# Top.net
KiCad netlist of a schematic drawn in Altium Designer
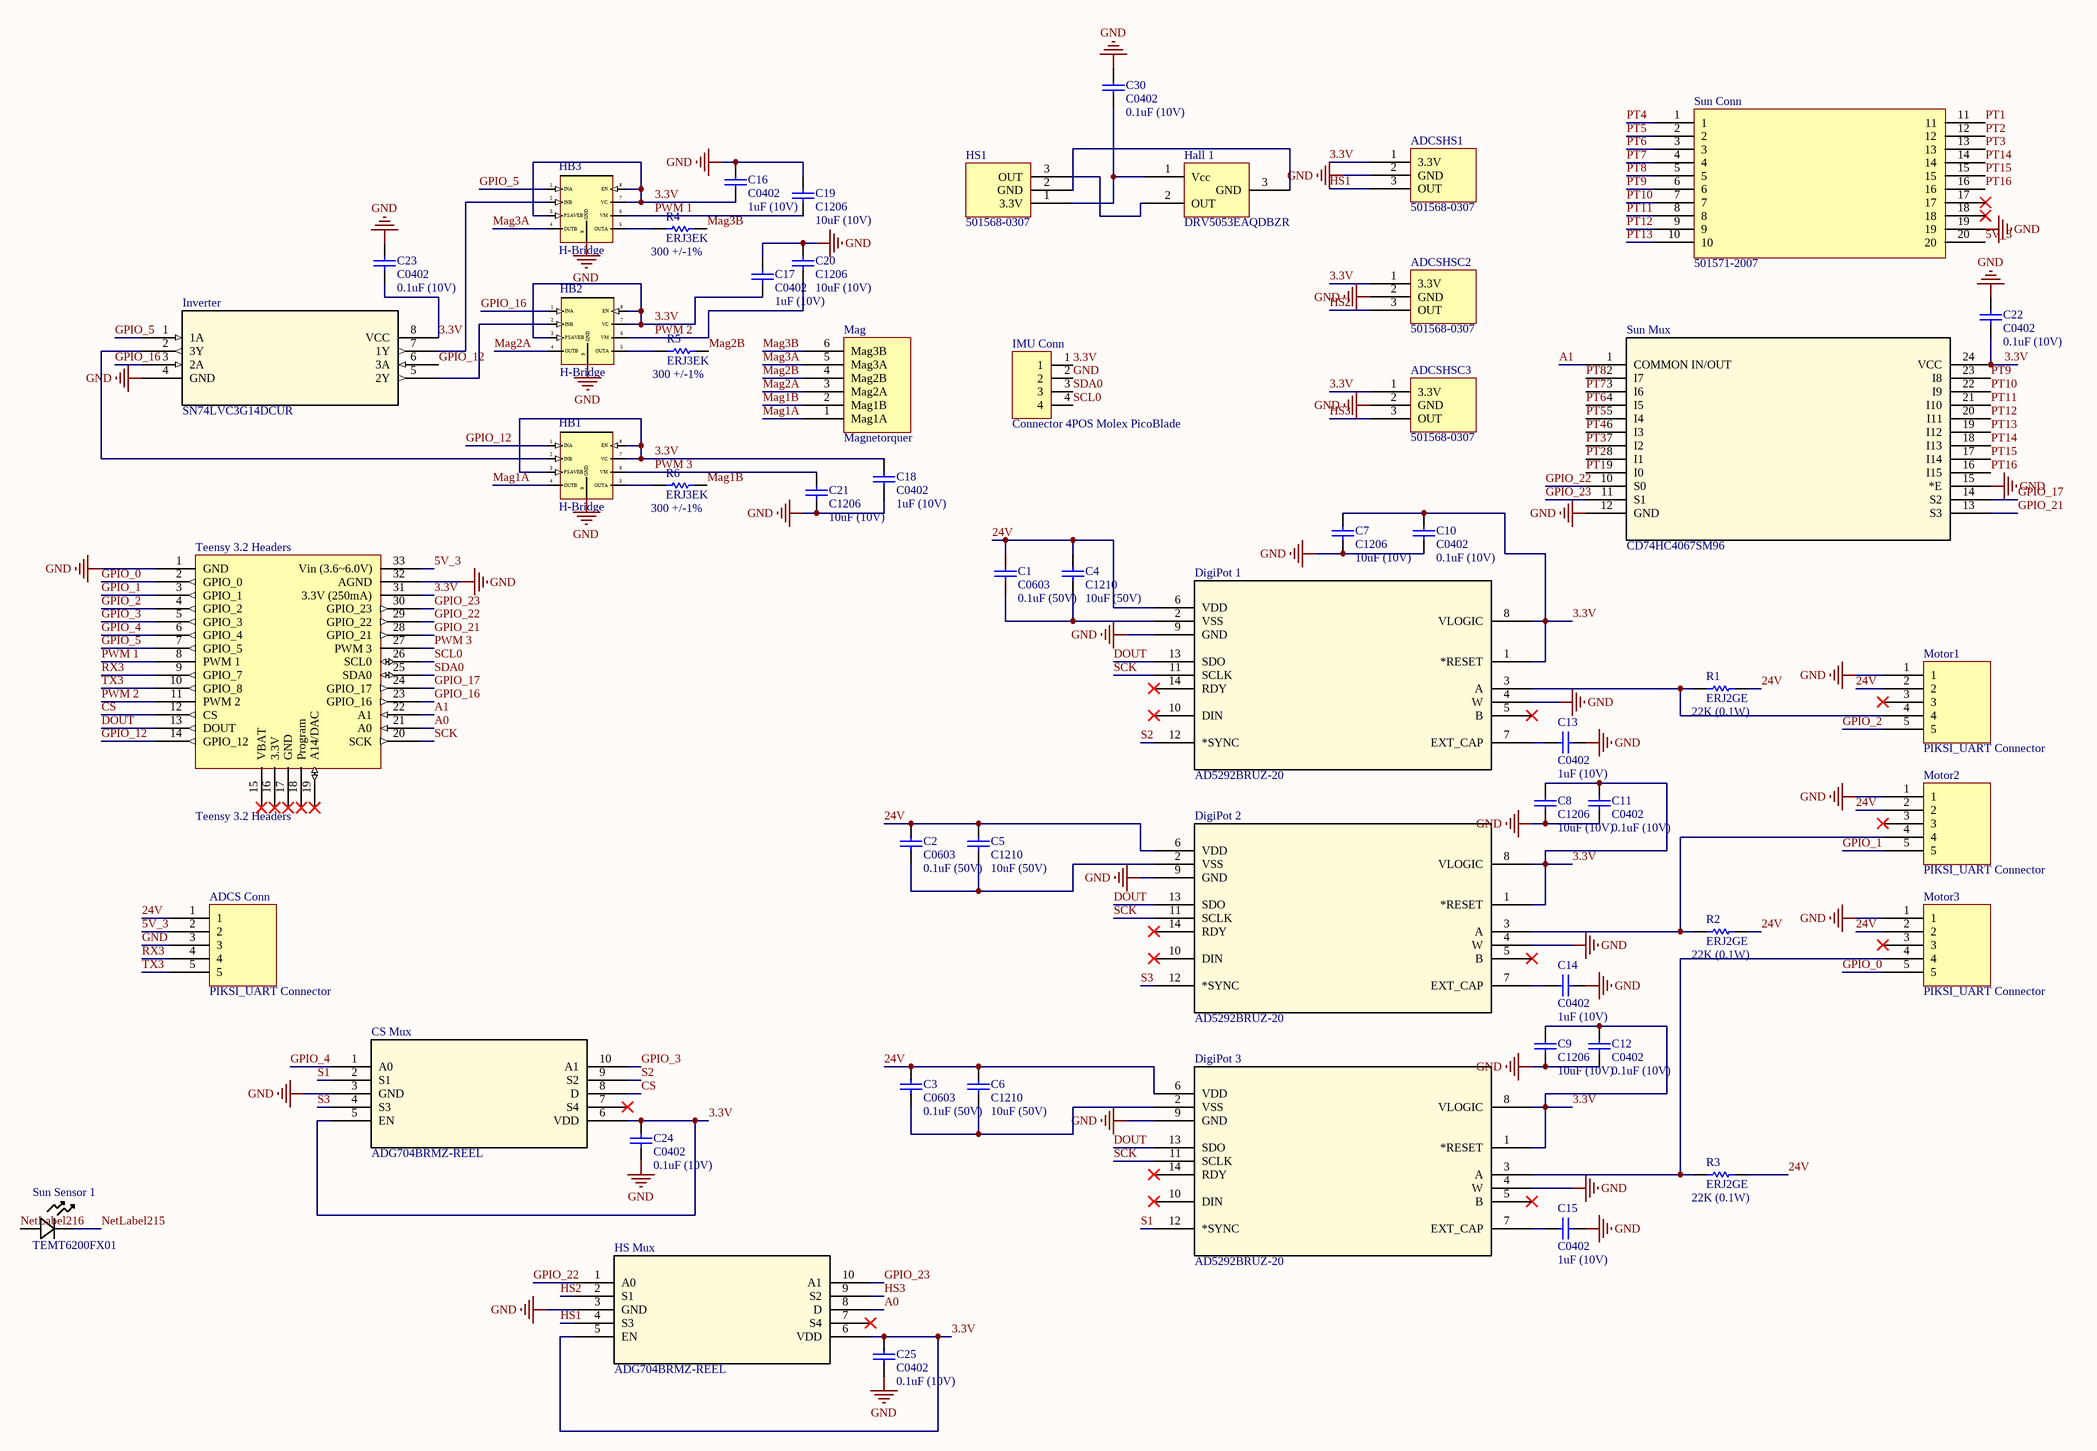
[diagram p0: Top.SchDoc]

(export (version "E")
  (design (tool "Eeschema 10.0.6"))
  (components
    (comp (ref "ADCS Conn")
      (value "PIKSI_UART Connector")
      (footprint "UmbilicalConnectors:Molex Picoblade 5 Pin")
      (description "Molex Picoblade 53261-0571")
      (libsource (lib "UmbilicalBoardV2") (part "PIKSI_UART Connector"))
    )
    (comp (ref "ADCSHS1")
      (value "501568-0307")
      (footprint "5015680307")
      (description "CONN HEADER 1MM 3POS")
      (libsource (lib "SchematicComponents") (part "501568-0307"))
    )
    (comp (ref "ADCSHSC2")
      (value "501568-0307")
      (footprint "5015680307")
      (description "CONN HEADER 1MM 3POS")
      (libsource (lib "SchematicComponents") (part "501568-0307"))
    )
    (comp (ref "ADCSHSC3")
      (value "501568-0307")
      (footprint "5015680307")
      (description "CONN HEADER 1MM 3POS")
      (libsource (lib "SchematicComponents") (part "501568-0307"))
    )
    (comp (ref "C1")
      (value "C0603")
      (footprint "0603")
      (description "Ceramic Chip Capacitor - Standard")
      (fields (field (name "ALTIUM_VALUE") "0.1uF (50V)") (field (name "PUBLISHER") "Altium Limited"))
      (libsource (lib "KEMET Chip Capacitor") (part "C0603"))
    )
    (comp (ref "C2")
      (value "C0603")
      (footprint "0603")
      (description "Ceramic Chip Capacitor - Standard")
      (fields (field (name "ALTIUM_VALUE") "0.1uF (50V)") (field (name "PUBLISHER") "Altium Limited"))
      (libsource (lib "KEMET Chip Capacitor") (part "C0603"))
    )
    (comp (ref "C3")
      (value "C0603")
      (footprint "0603")
      (description "Ceramic Chip Capacitor - Standard")
      (fields (field (name "ALTIUM_VALUE") "0.1uF (50V)") (field (name "PUBLISHER") "Altium Limited"))
      (libsource (lib "KEMET Chip Capacitor") (part "C0603"))
    )
    (comp (ref "C4")
      (value "C1210")
      (footprint "1210")
      (description "Ceramic Chip Capacitor - Standard")
      (fields (field (name "ALTIUM_VALUE") "10uF (50V)") (field (name "PUBLISHER") "Altium Limited"))
      (libsource (lib "KEMET Chip Capacitor") (part "C1210"))
    )
    (comp (ref "C5")
      (value "C1210")
      (footprint "1210")
      (description "Ceramic Chip Capacitor - Standard")
      (fields (field (name "ALTIUM_VALUE") "10uF (50V)") (field (name "PUBLISHER") "Altium Limited"))
      (libsource (lib "KEMET Chip Capacitor") (part "C1210"))
    )
    (comp (ref "C6")
      (value "C1210")
      (footprint "1210")
      (description "Ceramic Chip Capacitor - Standard")
      (fields (field (name "ALTIUM_VALUE") "10uF (50V)") (field (name "PUBLISHER") "Altium Limited"))
      (libsource (lib "KEMET Chip Capacitor") (part "C1210"))
    )
    (comp (ref "C7")
      (value "C1206")
      (footprint "1206")
      (description "Ceramic Chip Capacitor - Standard")
      (fields (field (name "ALTIUM_VALUE") "10uF (10V)") (field (name "PUBLISHER") "Altium Limited"))
      (libsource (lib "KEMET Chip Capacitor") (part "C1206"))
    )
    (comp (ref "C8")
      (value "C1206")
      (footprint "1206")
      (description "Ceramic Chip Capacitor - Standard")
      (fields (field (name "ALTIUM_VALUE") "10uF (10V)") (field (name "PUBLISHER") "Altium Limited"))
      (libsource (lib "KEMET Chip Capacitor") (part "C1206"))
    )
    (comp (ref "C9")
      (value "C1206")
      (footprint "1206")
      (description "Ceramic Chip Capacitor - Standard")
      (fields (field (name "ALTIUM_VALUE") "10uF (10V)") (field (name "PUBLISHER") "Altium Limited"))
      (libsource (lib "KEMET Chip Capacitor") (part "C1206"))
    )
    (comp (ref "C10")
      (value "C0402")
      (footprint "0402")
      (description "Ceramic Chip Capacitor - Standard")
      (fields (field (name "ALTIUM_VALUE") "0.1uF (10V)") (field (name "PUBLISHER") "Altium Limited"))
      (libsource (lib "KEMET Chip Capacitor") (part "C0402"))
    )
    (comp (ref "C11")
      (value "C0402")
      (footprint "0402")
      (description "Ceramic Chip Capacitor - Standard")
      (fields (field (name "ALTIUM_VALUE") "0.1uF (10V)") (field (name "PUBLISHER") "Altium Limited"))
      (libsource (lib "KEMET Chip Capacitor") (part "C0402"))
    )
    (comp (ref "C12")
      (value "C0402")
      (footprint "0402")
      (description "Ceramic Chip Capacitor - Standard")
      (fields (field (name "ALTIUM_VALUE") "0.1uF (10V)") (field (name "PUBLISHER") "Altium Limited"))
      (libsource (lib "KEMET Chip Capacitor") (part "C0402"))
    )
    (comp (ref "C13")
      (value "C0402")
      (footprint "0402")
      (description "Ceramic Chip Capacitor - Standard")
      (fields (field (name "ALTIUM_VALUE") "1uF (10V)") (field (name "PUBLISHER") "Altium Limited"))
      (libsource (lib "KEMET Chip Capacitor") (part "C0402"))
    )
    (comp (ref "C14")
      (value "C0402")
      (footprint "0402")
      (description "Ceramic Chip Capacitor - Standard")
      (fields (field (name "ALTIUM_VALUE") "1uF (10V)") (field (name "PUBLISHER") "Altium Limited"))
      (libsource (lib "KEMET Chip Capacitor") (part "C0402"))
    )
    (comp (ref "C15")
      (value "C0402")
      (footprint "0402")
      (description "Ceramic Chip Capacitor - Standard")
      (fields (field (name "ALTIUM_VALUE") "1uF (10V)") (field (name "PUBLISHER") "Altium Limited"))
      (libsource (lib "KEMET Chip Capacitor") (part "C0402"))
    )
    (comp (ref "C16")
      (value "C0402")
      (footprint "0402")
      (description "Ceramic Chip Capacitor - Standard")
      (fields (field (name "ALTIUM_VALUE") "1uF (10V)") (field (name "PUBLISHER") "Altium Limited"))
      (libsource (lib "KEMET Chip Capacitor") (part "C0402"))
    )
    (comp (ref "C17")
      (value "C0402")
      (footprint "0402")
      (description "Ceramic Chip Capacitor - Standard")
      (fields (field (name "ALTIUM_VALUE") "1uF (10V)") (field (name "PUBLISHER") "Altium Limited"))
      (libsource (lib "KEMET Chip Capacitor") (part "C0402"))
    )
    (comp (ref "C18")
      (value "C0402")
      (footprint "0402")
      (description "Ceramic Chip Capacitor - Standard")
      (fields (field (name "ALTIUM_VALUE") "1uF (10V)") (field (name "PUBLISHER") "Altium Limited"))
      (libsource (lib "KEMET Chip Capacitor") (part "C0402"))
    )
    (comp (ref "C19")
      (value "C1206")
      (footprint "1206")
      (description "Ceramic Chip Capacitor - Standard")
      (fields (field (name "ALTIUM_VALUE") "10uF (10V)") (field (name "PUBLISHER") "Altium Limited"))
      (libsource (lib "KEMET Chip Capacitor") (part "C1206"))
    )
    (comp (ref "C20")
      (value "C1206")
      (footprint "1206")
      (description "Ceramic Chip Capacitor - Standard")
      (fields (field (name "ALTIUM_VALUE") "10uF (10V)") (field (name "PUBLISHER") "Altium Limited"))
      (libsource (lib "KEMET Chip Capacitor") (part "C1206"))
    )
    (comp (ref "C21")
      (value "C1206")
      (footprint "1206")
      (description "Ceramic Chip Capacitor - Standard")
      (fields (field (name "ALTIUM_VALUE") "10uF (10V)") (field (name "PUBLISHER") "Altium Limited"))
      (libsource (lib "KEMET Chip Capacitor") (part "C1206"))
    )
    (comp (ref "C22")
      (value "C0402")
      (footprint "0402")
      (description "Ceramic Chip Capacitor - Standard")
      (fields (field (name "ALTIUM_VALUE") "0.1uF (10V)") (field (name "PUBLISHER") "Altium Limited"))
      (libsource (lib "KEMET Chip Capacitor") (part "C0402"))
    )
    (comp (ref "C23")
      (value "C0402")
      (footprint "0402")
      (description "Ceramic Chip Capacitor - Standard")
      (fields (field (name "ALTIUM_VALUE") "0.1uF (10V)") (field (name "PUBLISHER") "Altium Limited"))
      (libsource (lib "KEMET Chip Capacitor") (part "C0402"))
    )
    (comp (ref "C24")
      (value "C0402")
      (footprint "0402")
      (description "Ceramic Chip Capacitor - Standard")
      (fields (field (name "ALTIUM_VALUE") "0.1uF (10V)") (field (name "PUBLISHER") "Altium Limited"))
      (libsource (lib "KEMET Chip Capacitor") (part "C0402"))
    )
    (comp (ref "C25")
      (value "C0402")
      (footprint "0402")
      (description "Ceramic Chip Capacitor - Standard")
      (fields (field (name "ALTIUM_VALUE") "0.1uF (10V)") (field (name "PUBLISHER") "Altium Limited"))
      (libsource (lib "KEMET Chip Capacitor") (part "C0402"))
    )
    (comp (ref "C30")
      (value "C0402")
      (footprint "0402")
      (description "Ceramic Chip Capacitor - Standard")
      (fields (field (name "ALTIUM_VALUE") "0.1uF (10V)") (field (name "PUBLISHER") "Altium Limited"))
      (libsource (lib "KEMET Chip Capacitor") (part "C0402"))
    )
    (comp (ref "CS Mux")
      (value "ADG704BRMZ-REEL")
      (footprint "ADG704BRMZ-REEL")
      (libsource (lib "SchematicComponents") (part "ADG704BRMZ-REEL"))
    )
    (comp (ref "DigiPot 1")
      (value "AD5292BRUZ-20")
      (footprint "AD5292BRUZ-20")
      (description "20K DigiPot 1024POS")
      (libsource (lib "SchematicComponents") (part "AD5292BRUZ-20"))
    )
    (comp (ref "DigiPot 2")
      (value "AD5292BRUZ-20")
      (footprint "AD5292BRUZ-20")
      (description "20K DigiPot 1024POS")
      (libsource (lib "SchematicComponents") (part "AD5292BRUZ-20"))
    )
    (comp (ref "DigiPot 3")
      (value "AD5292BRUZ-20")
      (footprint "AD5292BRUZ-20")
      (description "20K DigiPot 1024POS")
      (libsource (lib "SchematicComponents") (part "AD5292BRUZ-20"))
    )
    (comp (ref "Hall 1")
      (value "DRV5053EAQDBZR")
      (footprint "DRV5053EAQDBZR")
      (description "Hall Sensor Linear SOT-23-3")
      (libsource (lib "SchematicComponents") (part "DRV5053EAQDBZR"))
    )
    (comp (ref "HB1")
      (value "H-Bridge")
      (footprint "AP1017")
      (libsource (lib "SchematicComponents") (part "AP1017AEN"))
    )
    (comp (ref "HB2")
      (value "H-Bridge")
      (footprint "AP1017")
      (libsource (lib "SchematicComponents") (part "AP1017AEN"))
    )
    (comp (ref "HB3")
      (value "H-Bridge")
      (footprint "AP1017")
      (libsource (lib "SchematicComponents") (part "AP1017AEN"))
    )
    (comp (ref "HS Mux")
      (value "ADG704BRMZ-REEL")
      (footprint "ADG704BRMZ-REEL")
      (libsource (lib "SchematicComponents") (part "ADG704BRMZ-REEL"))
    )
    (comp (ref "HS1")
      (value "501568-0307")
      (footprint "5015680307")
      (description "CONN HEADER 1MM 3POS")
      (libsource (lib "") (part "501568-0307_1"))
    )
    (comp (ref "IMU Conn")
      (value "Connector 4POS Molex PicoBlade")
      (footprint "532610471")
      (libsource (lib "SchematicComponents") (part "532610471"))
    )
    (comp (ref "Inverter")
      (value "SN74LVC3G14DCUR")
      (footprint "SN74LVC3G14DCUR")
      (libsource (lib "SchematicComponents") (part "SN74LVC3G14DCUR"))
    )
    (comp (ref "Mag")
      (value "Magnetorquer")
      (description "Molex 70553-0005")
      (libsource (lib "UmbilicalBoardV2") (part "PressureConnector"))
    )
    (comp (ref "Motor1")
      (value "PIKSI_UART Connector")
      (footprint "UmbilicalConnectors:Molex Picoblade 5 Pin")
      (description "Molex Picoblade 53261-0571")
      (libsource (lib "UmbilicalBoardV2") (part "PIKSI_UART Connector"))
    )
    (comp (ref "Motor2")
      (value "PIKSI_UART Connector")
      (footprint "UmbilicalConnectors:Molex Picoblade 5 Pin")
      (description "Molex Picoblade 53261-0571")
      (libsource (lib "UmbilicalBoardV2") (part "PIKSI_UART Connector"))
    )
    (comp (ref "Motor3")
      (value "PIKSI_UART Connector")
      (footprint "UmbilicalConnectors:Molex Picoblade 5 Pin")
      (description "Molex Picoblade 53261-0571")
      (libsource (lib "UmbilicalBoardV2") (part "PIKSI_UART Connector"))
    )
    (comp (ref "R1")
      (value "ERJ2GE")
      (footprint "2-0402")
      (description "Thick Film Chip Resistor, 1 Ohm to 2.2M Ohm Range, 5% Tolerance, 0402 Size, 0.063 W")
      (fields (field (name "ALTIUM_VALUE") "22K (0.1W)") (field (name "PUBLISHER") "Altium Limited"))
      (libsource (lib "Panasonic Resistor") (part "ERJ2GE"))
    )
    (comp (ref "R2")
      (value "ERJ2GE")
      (footprint "2-0402")
      (description "Thick Film Chip Resistor, 1 Ohm to 2.2M Ohm Range, 5% Tolerance, 0402 Size, 0.063 W")
      (fields (field (name "ALTIUM_VALUE") "22K (0.1W)") (field (name "PUBLISHER") "Altium Limited"))
      (libsource (lib "Panasonic Resistor") (part "ERJ2GE"))
    )
    (comp (ref "R3")
      (value "ERJ2GE")
      (footprint "2-0402")
      (description "Thick Film Chip Resistor, 1 Ohm to 2.2M Ohm Range, 5% Tolerance, 0402 Size, 0.063 W")
      (fields (field (name "ALTIUM_VALUE") "22K (0.1W)") (field (name "PUBLISHER") "Altium Limited"))
      (libsource (lib "Panasonic Resistor") (part "ERJ2GE"))
    )
    (comp (ref "R4")
      (value "ERJ3EK")
      (footprint "3-0603")
      (fields (field (name "RESISTANCE") "300 +/-1%") (field (name "PUBLISHER") "Altium Limited"))
      (libsource (lib "Panasonic Resistor") (part "ERJ3EK"))
    )
    (comp (ref "R5")
      (value "ERJ3EK")
      (footprint "3-0603")
      (fields (field (name "RESISTANCE") "300 +/-1%") (field (name "PUBLISHER") "Altium Limited"))
      (libsource (lib "Panasonic Resistor") (part "ERJ3EK"))
    )
    (comp (ref "R6")
      (value "ERJ3EK")
      (footprint "3-0603")
      (fields (field (name "RESISTANCE") "300 +/-1%") (field (name "PUBLISHER") "Altium Limited"))
      (libsource (lib "Panasonic Resistor") (part "ERJ3EK"))
    )
    (comp (ref "Sun Conn")
      (value "501571-2007")
      (footprint "501571-2007 20Pos Conn")
      (description "Pico-Clasp 1.0mm 20POS")
      (libsource (lib "SchematicComponents") (part "501571-2007"))
    )
    (comp (ref "Sun Mux")
      (value "CD74HC4067SM96")
      (footprint "CD74HC4067SM96")
      (libsource (lib "SchematicComponents") (part "CD74HC4067SM96"))
    )
    (comp (ref "Sun Sensor 1")
      (value "TEMT6200FX01")
      (footprint "Phototransistor")
      (libsource (lib "SchematicComponents") (part "TEMT6200FX01"))
    )
    (comp (ref "Teensy 3.2 Headers")
      (value "Teensy 3.2 Headers")
      (footprint "Teensy 3.2 with Headers")
      (libsource (lib "SchematicComponents") (part "Teensy 3.2 Headers"))
    )
  )
  (nets
    (net (code "1") (name "/3.3V") (class "Default")
      (node (ref "ADCSHS1") (pin "1") (pinfunction "3.3V_1") (pintype "power_in"))
      (node (ref "ADCSHSC2") (pin "1") (pinfunction "3.3V_1") (pintype "power_in"))
      (node (ref "ADCSHSC3") (pin "1") (pinfunction "3.3V_1") (pintype "power_in"))
      (node (ref "C10") (pin "2") (pinfunction "2_2") (pintype "passive"))
      (node (ref "C11") (pin "2") (pinfunction "2_2") (pintype "passive"))
      (node (ref "C12") (pin "2") (pinfunction "2_2") (pintype "passive"))
      (node (ref "C16") (pin "1") (pinfunction "1_1") (pintype "passive"))
      (node (ref "C17") (pin "1") (pinfunction "1_1") (pintype "passive"))
      (node (ref "C18") (pin "2") (pinfunction "2_2") (pintype "passive"))
      (node (ref "C22") (pin "1") (pinfunction "1_1") (pintype "passive"))
      (node (ref "C23") (pin "1") (pinfunction "1_1") (pintype "passive"))
      (node (ref "C24") (pin "2") (pinfunction "2_2") (pintype "passive"))
      (node (ref "C25") (pin "2") (pinfunction "2_2") (pintype "passive"))
      (node (ref "C7") (pin "2") (pinfunction "2_2") (pintype "passive"))
      (node (ref "C8") (pin "2") (pinfunction "2_2") (pintype "passive"))
      (node (ref "C9") (pin "2") (pinfunction "2_2") (pintype "passive"))
      (node (ref "CS Mux") (pin "5") (pinfunction "EN_5") (pintype "passive"))
      (node (ref "CS Mux") (pin "6") (pinfunction "VDD_6") (pintype "power_in"))
      (node (ref "DigiPot 1") (pin "1") (pinfunction "*RESET_1") (pintype "passive"))
      (node (ref "DigiPot 1") (pin "8") (pinfunction "VLOGIC_8") (pintype "passive"))
      (node (ref "DigiPot 2") (pin "1") (pinfunction "*RESET_1") (pintype "passive"))
      (node (ref "DigiPot 2") (pin "8") (pinfunction "VLOGIC_8") (pintype "passive"))
      (node (ref "DigiPot 3") (pin "1") (pinfunction "*RESET_1") (pintype "passive"))
      (node (ref "DigiPot 3") (pin "8") (pinfunction "VLOGIC_8") (pintype "passive"))
      (node (ref "HB1") (pin "3") (pinfunction "PSAVEB_3") (pintype "input"))
      (node (ref "HB1") (pin "7") (pinfunction "VC_7") (pintype "power_in"))
      (node (ref "HB1") (pin "8") (pinfunction "EN_8") (pintype "input"))
      (node (ref "HB2") (pin "3") (pinfunction "PSAVEB_3") (pintype "input"))
      (node (ref "HB2") (pin "7") (pinfunction "VC_7") (pintype "power_in"))
      (node (ref "HB2") (pin "8") (pinfunction "EN_8") (pintype "input"))
      (node (ref "HB3") (pin "3") (pinfunction "PSAVEB_3") (pintype "input"))
      (node (ref "HB3") (pin "7") (pinfunction "VC_7") (pintype "power_in"))
      (node (ref "HB3") (pin "8") (pinfunction "EN_8") (pintype "input"))
      (node (ref "HS Mux") (pin "5") (pinfunction "EN_5") (pintype "passive"))
      (node (ref "HS Mux") (pin "6") (pinfunction "VDD_6") (pintype "power_in"))
      (node (ref "IMU Conn") (pin "1") (pinfunction "1_1") (pintype "passive"))
      (node (ref "Inverter") (pin "8") (pinfunction "VCC_8") (pintype "power_in"))
      (node (ref "Sun Mux") (pin "24") (pinfunction "VCC_24") (pintype "power_in"))
      (node (ref "Teensy 3.2 Headers") (pin "31") (pinfunction "3.3V_(250mA)_31") (pintype "power_in"))
    )
    (net (code "2") (name "/5V_3") (class "Default")
      (node (ref "ADCS Conn") (pin "2") (pinfunction "2_2") (pintype "passive"))
      (node (ref "Sun Conn") (pin "20") (pinfunction "20_20") (pintype "passive"))
      (node (ref "Teensy 3.2 Headers") (pin "33") (pinfunction "Vin_(3.6~6.0V)_33") (pintype "power_in"))
    )
    (net (code "3") (name "/24V") (class "Default")
      (node (ref "ADCS Conn") (pin "1") (pinfunction "1_1") (pintype "passive"))
      (node (ref "C1") (pin "2") (pinfunction "2_2") (pintype "passive"))
      (node (ref "C2") (pin "2") (pinfunction "2_2") (pintype "passive"))
      (node (ref "C3") (pin "2") (pinfunction "2_2") (pintype "passive"))
      (node (ref "C4") (pin "2") (pinfunction "2_2") (pintype "passive"))
      (node (ref "C5") (pin "2") (pinfunction "2_2") (pintype "passive"))
      (node (ref "C6") (pin "2") (pinfunction "2_2") (pintype "passive"))
      (node (ref "DigiPot 1") (pin "6") (pinfunction "VDD_6") (pintype "passive"))
      (node (ref "DigiPot 2") (pin "6") (pinfunction "VDD_6") (pintype "passive"))
      (node (ref "DigiPot 3") (pin "6") (pinfunction "VDD_6") (pintype "passive"))
      (node (ref "Motor1") (pin "2") (pinfunction "2_2") (pintype "passive"))
      (node (ref "Motor2") (pin "2") (pinfunction "2_2") (pintype "passive"))
      (node (ref "Motor3") (pin "2") (pinfunction "2_2") (pintype "passive"))
      (node (ref "R1") (pin "2") (pinfunction "2_2") (pintype "passive"))
      (node (ref "R2") (pin "2") (pinfunction "2_2") (pintype "passive"))
      (node (ref "R3") (pin "2") (pinfunction "2_2") (pintype "passive"))
    )
    (net (code "4") (name "/A0") (class "Default")
      (node (ref "HS Mux") (pin "8") (pinfunction "D_8") (pintype "passive"))
      (node (ref "Teensy 3.2 Headers") (pin "21") (pinfunction "A0_21") (pintype "input"))
    )
    (net (code "5") (name "/A1") (class "Default")
      (node (ref "Sun Mux") (pin "1") (pinfunction "COMMON_IN/OUT_1") (pintype "passive"))
      (node (ref "Teensy 3.2 Headers") (pin "22") (pinfunction "A1_22") (pintype "input"))
    )
    (net (code "6") (name "/CS") (class "Default")
      (node (ref "CS Mux") (pin "8") (pinfunction "D_8") (pintype "passive"))
      (node (ref "Teensy 3.2 Headers") (pin "12") (pinfunction "CS_12") (pintype "output"))
    )
    (net (code "7") (name "/DOUT") (class "Default")
      (node (ref "DigiPot 1") (pin "13") (pinfunction "SDO_13") (pintype "passive"))
      (node (ref "DigiPot 2") (pin "13") (pinfunction "SDO_13") (pintype "passive"))
      (node (ref "DigiPot 3") (pin "13") (pinfunction "SDO_13") (pintype "passive"))
      (node (ref "Teensy 3.2 Headers") (pin "13") (pinfunction "DOUT_13") (pintype "output"))
    )
    (net (code "8") (name "/GPIO_0") (class "Default")
      (node (ref "Motor3") (pin "5") (pinfunction "5_5") (pintype "passive"))
      (node (ref "Teensy 3.2 Headers") (pin "2") (pinfunction "GPIO_0_2") (pintype "output"))
    )
    (net (code "9") (name "/GPIO_1") (class "Default")
      (node (ref "Motor2") (pin "5") (pinfunction "5_5") (pintype "passive"))
      (node (ref "Teensy 3.2 Headers") (pin "3") (pinfunction "GPIO_1_3") (pintype "output"))
    )
    (net (code "10") (name "/GPIO_2") (class "Default")
      (node (ref "Motor1") (pin "5") (pinfunction "5_5") (pintype "passive"))
      (node (ref "Teensy 3.2 Headers") (pin "4") (pinfunction "GPIO_2_4") (pintype "output"))
    )
    (net (code "11") (name "/GPIO_3") (class "Default")
      (node (ref "CS Mux") (pin "10") (pinfunction "A1_10") (pintype "passive"))
      (node (ref "Teensy 3.2 Headers") (pin "5") (pinfunction "GPIO_3_5") (pintype "output"))
    )
    (net (code "12") (name "/GPIO_4") (class "Default")
      (node (ref "CS Mux") (pin "1") (pinfunction "A0_1") (pintype "passive"))
      (node (ref "Teensy 3.2 Headers") (pin "6") (pinfunction "GPIO_4_6") (pintype "output"))
    )
    (net (code "13") (name "/GPIO_5") (class "Default")
      (node (ref "HB3") (pin "1") (pinfunction "INA_1") (pintype "input"))
      (node (ref "Inverter") (pin "1") (pinfunction "1A_1") (pintype "input"))
      (node (ref "Teensy 3.2 Headers") (pin "7") (pinfunction "GPIO_5_7") (pintype "output"))
    )
    (net (code "14") (name "/GPIO_12") (class "Default")
      (node (ref "HB1") (pin "1") (pinfunction "INA_1") (pintype "input"))
      (node (ref "Inverter") (pin "6") (pinfunction "3A_6") (pintype "input"))
      (node (ref "Teensy 3.2 Headers") (pin "14") (pinfunction "GPIO_12_14") (pintype "output"))
    )
    (net (code "15") (name "/GPIO_16") (class "Default")
      (node (ref "HB2") (pin "1") (pinfunction "INA_1") (pintype "input"))
      (node (ref "Inverter") (pin "3") (pinfunction "2A_3") (pintype "input"))
      (node (ref "Teensy 3.2 Headers") (pin "23") (pinfunction "GPIO_16_23") (pintype "output"))
    )
    (net (code "16") (name "/GPIO_17") (class "Default")
      (node (ref "Sun Mux") (pin "14") (pinfunction "S2_14") (pintype "passive"))
      (node (ref "Teensy 3.2 Headers") (pin "24") (pinfunction "GPIO_17_24") (pintype "output"))
    )
    (net (code "17") (name "/GPIO_21") (class "Default")
      (node (ref "Sun Mux") (pin "13") (pinfunction "S3_13") (pintype "passive"))
      (node (ref "Teensy 3.2 Headers") (pin "28") (pinfunction "GPIO_21_28") (pintype "output"))
    )
    (net (code "18") (name "/GPIO_22") (class "Default")
      (node (ref "HS Mux") (pin "1") (pinfunction "A0_1") (pintype "passive"))
      (node (ref "Sun Mux") (pin "10") (pinfunction "S0_10") (pintype "passive"))
      (node (ref "Teensy 3.2 Headers") (pin "29") (pinfunction "GPIO_22_29") (pintype "output"))
    )
    (net (code "19") (name "/GPIO_23") (class "Default")
      (node (ref "HS Mux") (pin "10") (pinfunction "A1_10") (pintype "passive"))
      (node (ref "Sun Mux") (pin "11") (pinfunction "S1_11") (pintype "passive"))
      (node (ref "Teensy 3.2 Headers") (pin "30") (pinfunction "GPIO_23_30") (pintype "output"))
    )
    (net (code "20") (name "/HS1") (class "Default")
      (node (ref "ADCSHS1") (pin "3") (pinfunction "OUT_3") (pintype "power_in"))
      (node (ref "HS Mux") (pin "4") (pinfunction "S3_4") (pintype "passive"))
    )
    (net (code "21") (name "/HS2") (class "Default")
      (node (ref "ADCSHSC2") (pin "3") (pinfunction "OUT_3") (pintype "power_in"))
      (node (ref "HS Mux") (pin "2") (pinfunction "S1_2") (pintype "passive"))
    )
    (net (code "22") (name "/HS3") (class "Default")
      (node (ref "ADCSHSC3") (pin "3") (pinfunction "OUT_3") (pintype "power_in"))
      (node (ref "HS Mux") (pin "9") (pinfunction "S2_9") (pintype "passive"))
    )
    (net (code "23") (name "/Mag1A") (class "Default")
      (node (ref "HB1") (pin "4") (pinfunction "OUTB_4") (pintype "power_in"))
      (node (ref "Mag") (pin "1") (pinfunction "Mag1A_1") (pintype "passive"))
    )
    (net (code "24") (name "/Mag1B") (class "Default")
      (node (ref "Mag") (pin "2") (pinfunction "Mag1B_2") (pintype "passive"))
      (node (ref "R6") (pin "2") (pinfunction "2_2") (pintype "passive"))
    )
    (net (code "25") (name "/Mag2A") (class "Default")
      (node (ref "HB2") (pin "4") (pinfunction "OUTB_4") (pintype "power_in"))
      (node (ref "Mag") (pin "3") (pinfunction "Mag2A_3") (pintype "passive"))
    )
    (net (code "26") (name "/Mag2B") (class "Default")
      (node (ref "Mag") (pin "4") (pinfunction "Mag2B_4") (pintype "passive"))
      (node (ref "R5") (pin "2") (pinfunction "2_2") (pintype "passive"))
    )
    (net (code "27") (name "/Mag3A") (class "Default")
      (node (ref "HB3") (pin "4") (pinfunction "OUTB_4") (pintype "power_in"))
      (node (ref "Mag") (pin "5") (pinfunction "Mag3A_5") (pintype "passive"))
    )
    (net (code "28") (name "/Mag3B") (class "Default")
      (node (ref "Mag") (pin "6") (pinfunction "Mag3B_6") (pintype "passive"))
      (node (ref "R4") (pin "2") (pinfunction "2_2") (pintype "passive"))
    )
    (net (code "29") (name "/NetLabel215") (class "Default")
      (node (ref "Sun Sensor 1") (pin "1") (pinfunction "1_1") (pintype "passive"))
    )
    (net (code "30") (name "/NetLabel216") (class "Default")
      (node (ref "Sun Sensor 1") (pin "2") (pinfunction "2_2") (pintype "passive"))
    )
    (net (code "31") (name "/PT1") (class "Default")
      (node (ref "Sun Conn") (pin "11") (pinfunction "11_11") (pintype "passive"))
      (node (ref "Sun Mux") (pin "9") (pinfunction "I0_9") (pintype "passive"))
    )
    (net (code "32") (name "/PT2") (class "Default")
      (node (ref "Sun Conn") (pin "12") (pinfunction "12_12") (pintype "passive"))
      (node (ref "Sun Mux") (pin "8") (pinfunction "I1_8") (pintype "passive"))
    )
    (net (code "33") (name "/PT3") (class "Default")
      (node (ref "Sun Conn") (pin "13") (pinfunction "13_13") (pintype "passive"))
      (node (ref "Sun Mux") (pin "7") (pinfunction "I2_7") (pintype "passive"))
    )
    (net (code "34") (name "/PT4") (class "Default")
      (node (ref "Sun Conn") (pin "1") (pinfunction "1_1") (pintype "passive"))
      (node (ref "Sun Mux") (pin "6") (pinfunction "I3_6") (pintype "passive"))
    )
    (net (code "35") (name "/PT5") (class "Default")
      (node (ref "Sun Conn") (pin "2") (pinfunction "2_2") (pintype "passive"))
      (node (ref "Sun Mux") (pin "5") (pinfunction "I4_5") (pintype "passive"))
    )
    (net (code "36") (name "/PT6") (class "Default")
      (node (ref "Sun Conn") (pin "3") (pinfunction "3_3") (pintype "passive"))
      (node (ref "Sun Mux") (pin "4") (pinfunction "I5_4") (pintype "passive"))
    )
    (net (code "37") (name "/PT7") (class "Default")
      (node (ref "Sun Conn") (pin "4") (pinfunction "4_4") (pintype "passive"))
      (node (ref "Sun Mux") (pin "3") (pinfunction "I6_3") (pintype "passive"))
    )
    (net (code "38") (name "/PT8") (class "Default")
      (node (ref "Sun Conn") (pin "5") (pinfunction "5_5") (pintype "passive"))
      (node (ref "Sun Mux") (pin "2") (pinfunction "I7_2") (pintype "passive"))
    )
    (net (code "39") (name "/PT9") (class "Default")
      (node (ref "Sun Conn") (pin "6") (pinfunction "6_6") (pintype "passive"))
      (node (ref "Sun Mux") (pin "23") (pinfunction "I8_23") (pintype "passive"))
    )
    (net (code "40") (name "/PT10") (class "Default")
      (node (ref "Sun Conn") (pin "7") (pinfunction "7_7") (pintype "passive"))
      (node (ref "Sun Mux") (pin "22") (pinfunction "I9_22") (pintype "passive"))
    )
    (net (code "41") (name "/PT11") (class "Default")
      (node (ref "Sun Conn") (pin "8") (pinfunction "8_8") (pintype "passive"))
      (node (ref "Sun Mux") (pin "21") (pinfunction "I10_21") (pintype "passive"))
    )
    (net (code "42") (name "/PT12") (class "Default")
      (node (ref "Sun Conn") (pin "9") (pinfunction "9_9") (pintype "passive"))
      (node (ref "Sun Mux") (pin "20") (pinfunction "I11_20") (pintype "passive"))
    )
    (net (code "43") (name "/PT13") (class "Default")
      (node (ref "Sun Conn") (pin "10") (pinfunction "10_10") (pintype "passive"))
      (node (ref "Sun Mux") (pin "19") (pinfunction "I12_19") (pintype "passive"))
    )
    (net (code "44") (name "/PT14") (class "Default")
      (node (ref "Sun Conn") (pin "14") (pinfunction "14_14") (pintype "passive"))
      (node (ref "Sun Mux") (pin "18") (pinfunction "I13_18") (pintype "passive"))
    )
    (net (code "45") (name "/PT15") (class "Default")
      (node (ref "Sun Conn") (pin "15") (pinfunction "15_15") (pintype "passive"))
      (node (ref "Sun Mux") (pin "17") (pinfunction "I14_17") (pintype "passive"))
    )
    (net (code "46") (name "/PT16") (class "Default")
      (node (ref "Sun Conn") (pin "16") (pinfunction "16_16") (pintype "passive"))
      (node (ref "Sun Mux") (pin "16") (pinfunction "I15_16") (pintype "passive"))
    )
    (net (code "47") (name "/PWM 1") (class "Default")
      (node (ref "C19") (pin "1") (pinfunction "1_1") (pintype "passive"))
      (node (ref "HB3") (pin "6") (pinfunction "VM_6") (pintype "power_in"))
      (node (ref "Teensy 3.2 Headers") (pin "8") (pinfunction "PWM_1_8") (pintype "power_in"))
    )
    (net (code "48") (name "/PWM 2") (class "Default")
      (node (ref "C20") (pin "1") (pinfunction "1_1") (pintype "passive"))
      (node (ref "HB2") (pin "6") (pinfunction "VM_6") (pintype "power_in"))
      (node (ref "Teensy 3.2 Headers") (pin "11") (pinfunction "PWM_2_11") (pintype "power_in"))
    )
    (net (code "49") (name "/PWM 3") (class "Default")
      (node (ref "C21") (pin "2") (pinfunction "2_2") (pintype "passive"))
      (node (ref "HB1") (pin "6") (pinfunction "VM_6") (pintype "power_in"))
      (node (ref "Teensy 3.2 Headers") (pin "27") (pinfunction "PWM_3_27") (pintype "power_in"))
    )
    (net (code "50") (name "/RX3") (class "Default")
      (node (ref "ADCS Conn") (pin "4") (pinfunction "4_4") (pintype "passive"))
      (node (ref "Teensy 3.2 Headers") (pin "9") (pinfunction "GPIO_7_9") (pintype "output"))
    )
    (net (code "51") (name "/S1") (class "Default")
      (node (ref "CS Mux") (pin "2") (pinfunction "S1_2") (pintype "passive"))
      (node (ref "DigiPot 3") (pin "12") (pinfunction "*SYNC_12") (pintype "passive"))
    )
    (net (code "52") (name "/S2") (class "Default")
      (node (ref "CS Mux") (pin "9") (pinfunction "S2_9") (pintype "passive"))
      (node (ref "DigiPot 1") (pin "12") (pinfunction "*SYNC_12") (pintype "passive"))
    )
    (net (code "53") (name "/S3") (class "Default")
      (node (ref "CS Mux") (pin "4") (pinfunction "S3_4") (pintype "passive"))
      (node (ref "DigiPot 2") (pin "12") (pinfunction "*SYNC_12") (pintype "passive"))
    )
    (net (code "54") (name "/SCK") (class "Default")
      (node (ref "DigiPot 1") (pin "11") (pinfunction "SCLK_11") (pintype "passive"))
      (node (ref "DigiPot 2") (pin "11") (pinfunction "SCLK_11") (pintype "passive"))
      (node (ref "DigiPot 3") (pin "11") (pinfunction "SCLK_11") (pintype "passive"))
      (node (ref "Teensy 3.2 Headers") (pin "20") (pinfunction "SCK_20") (pintype "output"))
    )
    (net (code "55") (name "/SCL0") (class "Default")
      (node (ref "IMU Conn") (pin "4") (pinfunction "4_4") (pintype "passive"))
      (node (ref "Teensy 3.2 Headers") (pin "26") (pinfunction "SCL0_26") (pintype "bidirectional"))
    )
    (net (code "56") (name "/SDA0") (class "Default")
      (node (ref "IMU Conn") (pin "3") (pinfunction "3_3") (pintype "passive"))
      (node (ref "Teensy 3.2 Headers") (pin "25") (pinfunction "SDA0_25") (pintype "bidirectional"))
    )
    (net (code "57") (name "/TX3") (class "Default")
      (node (ref "ADCS Conn") (pin "5") (pinfunction "5_5") (pintype "passive"))
      (node (ref "Teensy 3.2 Headers") (pin "10") (pinfunction "GPIO_8_10") (pintype "output"))
    )
    (net (code "58") (name "GND") (class "Default")
      (node (ref "ADCS Conn") (pin "3") (pinfunction "3_3") (pintype "passive"))
      (node (ref "ADCSHS1") (pin "2") (pinfunction "GND_2") (pintype "passive"))
      (node (ref "ADCSHSC2") (pin "2") (pinfunction "GND_2") (pintype "passive"))
      (node (ref "ADCSHSC3") (pin "2") (pinfunction "GND_2") (pintype "passive"))
      (node (ref "C10") (pin "1") (pinfunction "1_1") (pintype "passive"))
      (node (ref "C11") (pin "1") (pinfunction "1_1") (pintype "passive"))
      (node (ref "C12") (pin "1") (pinfunction "1_1") (pintype "passive"))
      (node (ref "C13") (pin "2") (pinfunction "2_2") (pintype "passive"))
      (node (ref "C14") (pin "2") (pinfunction "2_2") (pintype "passive"))
      (node (ref "C15") (pin "2") (pinfunction "2_2") (pintype "passive"))
      (node (ref "C16") (pin "2") (pinfunction "2_2") (pintype "passive"))
      (node (ref "C17") (pin "2") (pinfunction "2_2") (pintype "passive"))
      (node (ref "C18") (pin "1") (pinfunction "1_1") (pintype "passive"))
      (node (ref "C19") (pin "2") (pinfunction "2_2") (pintype "passive"))
      (node (ref "C20") (pin "2") (pinfunction "2_2") (pintype "passive"))
      (node (ref "C21") (pin "1") (pinfunction "1_1") (pintype "passive"))
      (node (ref "C22") (pin "2") (pinfunction "2_2") (pintype "passive"))
      (node (ref "C23") (pin "2") (pinfunction "2_2") (pintype "passive"))
      (node (ref "C24") (pin "1") (pinfunction "1_1") (pintype "passive"))
      (node (ref "C25") (pin "1") (pinfunction "1_1") (pintype "passive"))
      (node (ref "C30") (pin "2") (pinfunction "2_2") (pintype "passive"))
      (node (ref "C7") (pin "1") (pinfunction "1_1") (pintype "passive"))
      (node (ref "C8") (pin "1") (pinfunction "1_1") (pintype "passive"))
      (node (ref "C9") (pin "1") (pinfunction "1_1") (pintype "passive"))
      (node (ref "CS Mux") (pin "3") (pinfunction "GND_3") (pintype "passive"))
      (node (ref "DigiPot 1") (pin "4") (pinfunction "W_4") (pintype "passive"))
      (node (ref "DigiPot 1") (pin "9") (pinfunction "GND_9") (pintype "passive"))
      (node (ref "DigiPot 2") (pin "4") (pinfunction "W_4") (pintype "passive"))
      (node (ref "DigiPot 2") (pin "9") (pinfunction "GND_9") (pintype "passive"))
      (node (ref "DigiPot 3") (pin "4") (pinfunction "W_4") (pintype "passive"))
      (node (ref "DigiPot 3") (pin "9") (pinfunction "GND_9") (pintype "passive"))
      (node (ref "HB1") (pin "9") (pinfunction "GND_9") (pintype "power_in"))
      (node (ref "HB2") (pin "9") (pinfunction "GND_9") (pintype "power_in"))
      (node (ref "HB3") (pin "9") (pinfunction "GND_9") (pintype "power_in"))
      (node (ref "HS Mux") (pin "3") (pinfunction "GND_3") (pintype "passive"))
      (node (ref "IMU Conn") (pin "2") (pinfunction "2_2") (pintype "passive"))
      (node (ref "Inverter") (pin "4") (pinfunction "GND_4") (pintype "power_in"))
      (node (ref "Motor1") (pin "1") (pinfunction "1_1") (pintype "passive"))
      (node (ref "Motor2") (pin "1") (pinfunction "1_1") (pintype "passive"))
      (node (ref "Motor3") (pin "1") (pinfunction "1_1") (pintype "passive"))
      (node (ref "Sun Conn") (pin "19") (pinfunction "19_19") (pintype "passive"))
      (node (ref "Sun Mux") (pin "12") (pinfunction "GND_12") (pintype "power_in"))
      (node (ref "Sun Mux") (pin "15") (pinfunction "*E_15") (pintype "passive"))
      (node (ref "Teensy 3.2 Headers") (pin "1") (pinfunction "GND_1") (pintype "power_in"))
      (node (ref "Teensy 3.2 Headers") (pin "32") (pinfunction "AGND_32") (pintype "power_in"))
    )
    (net (code "59") (name "Net-(DigiPot 1-A)") (class "Default")
      (node (ref "DigiPot 1") (pin "3") (pinfunction "A_3") (pintype "passive"))
      (node (ref "Motor1") (pin "4") (pinfunction "4_4") (pintype "passive"))
      (node (ref "R1") (pin "1") (pinfunction "1_1") (pintype "passive"))
    )
    (net (code "60") (name "Net-(DigiPot 1-EXT_CAP)") (class "Default")
      (node (ref "C13") (pin "1") (pinfunction "1_1") (pintype "passive"))
      (node (ref "DigiPot 1") (pin "7") (pinfunction "EXT_CAP_7") (pintype "passive"))
    )
    (net (code "61") (name "Net-(DigiPot 1-VSS)") (class "Default")
      (node (ref "C1") (pin "1") (pinfunction "1_1") (pintype "passive"))
      (node (ref "C4") (pin "1") (pinfunction "1_1") (pintype "passive"))
      (node (ref "DigiPot 1") (pin "2") (pinfunction "VSS_2") (pintype "passive"))
    )
    (net (code "62") (name "Net-(DigiPot 2-A)") (class "Default")
      (node (ref "DigiPot 2") (pin "3") (pinfunction "A_3") (pintype "passive"))
      (node (ref "Motor2") (pin "4") (pinfunction "4_4") (pintype "passive"))
      (node (ref "R2") (pin "1") (pinfunction "1_1") (pintype "passive"))
    )
    (net (code "63") (name "Net-(DigiPot 2-EXT_CAP)") (class "Default")
      (node (ref "C14") (pin "1") (pinfunction "1_1") (pintype "passive"))
      (node (ref "DigiPot 2") (pin "7") (pinfunction "EXT_CAP_7") (pintype "passive"))
    )
    (net (code "64") (name "Net-(DigiPot 2-VSS)") (class "Default")
      (node (ref "C2") (pin "1") (pinfunction "1_1") (pintype "passive"))
      (node (ref "C5") (pin "1") (pinfunction "1_1") (pintype "passive"))
      (node (ref "DigiPot 2") (pin "2") (pinfunction "VSS_2") (pintype "passive"))
    )
    (net (code "65") (name "Net-(DigiPot 3-A)") (class "Default")
      (node (ref "DigiPot 3") (pin "3") (pinfunction "A_3") (pintype "passive"))
      (node (ref "Motor3") (pin "4") (pinfunction "4_4") (pintype "passive"))
      (node (ref "R3") (pin "1") (pinfunction "1_1") (pintype "passive"))
    )
    (net (code "66") (name "Net-(DigiPot 3-EXT_CAP)") (class "Default")
      (node (ref "C15") (pin "1") (pinfunction "1_1") (pintype "passive"))
      (node (ref "DigiPot 3") (pin "7") (pinfunction "EXT_CAP_7") (pintype "passive"))
    )
    (net (code "67") (name "Net-(DigiPot 3-VSS)") (class "Default")
      (node (ref "C3") (pin "1") (pinfunction "1_1") (pintype "passive"))
      (node (ref "C6") (pin "1") (pinfunction "1_1") (pintype "passive"))
      (node (ref "DigiPot 3") (pin "2") (pinfunction "VSS_2") (pintype "passive"))
    )
    (net (code "68") (name "Net-(HB1-INB)") (class "Default")
      (node (ref "HB1") (pin "2") (pinfunction "INB_2") (pintype "input"))
      (node (ref "Inverter") (pin "2") (pinfunction "3Y_2") (pintype "output"))
    )
    (net (code "69") (name "Net-(HB1-OUTA)") (class "Default")
      (node (ref "HB1") (pin "5") (pinfunction "OUTA_5") (pintype "power_in"))
      (node (ref "R6") (pin "1") (pinfunction "1_1") (pintype "passive"))
    )
    (net (code "70") (name "Net-(HB2-INB)") (class "Default")
      (node (ref "HB2") (pin "2") (pinfunction "INB_2") (pintype "input"))
      (node (ref "Inverter") (pin "5") (pinfunction "2Y_5") (pintype "output"))
    )
    (net (code "71") (name "Net-(HB2-OUTA)") (class "Default")
      (node (ref "HB2") (pin "5") (pinfunction "OUTA_5") (pintype "power_in"))
      (node (ref "R5") (pin "1") (pinfunction "1_1") (pintype "passive"))
    )
    (net (code "72") (name "Net-(HB3-INB)") (class "Default")
      (node (ref "HB3") (pin "2") (pinfunction "INB_2") (pintype "input"))
      (node (ref "Inverter") (pin "7") (pinfunction "1Y_7") (pintype "output"))
    )
    (net (code "73") (name "Net-(HB3-OUTA)") (class "Default")
      (node (ref "HB3") (pin "5") (pinfunction "OUTA_5") (pintype "power_in"))
      (node (ref "R4") (pin "1") (pinfunction "1_1") (pintype "passive"))
    )
    (net (code "74") (name "Net-(HS1-3.3V)") (class "Default")
      (node (ref "C30") (pin "1") (pinfunction "1_1") (pintype "passive"))
      (node (ref "HS1") (pin "1") (pinfunction "3.3V_1") (pintype "power_in"))
      (node (ref "Hall 1") (pin "1") (pinfunction "Vcc_1") (pintype "power_in"))
    )
    (net (code "75") (name "Net-(HS1-GND)") (class "Default")
      (node (ref "HS1") (pin "2") (pinfunction "GND_2") (pintype "passive"))
      (node (ref "Hall 1") (pin "3") (pinfunction "GND_3") (pintype "power_in"))
    )
    (net (code "76") (name "Net-(HS1-OUT)") (class "Default")
      (node (ref "HS1") (pin "3") (pinfunction "OUT_3") (pintype "power_in"))
      (node (ref "Hall 1") (pin "2") (pinfunction "OUT_2") (pintype "passive"))
    )
    (net (code "77") (name "unconnected-(CS Mux-S4-Pad7)") (class "Default")
      (node (ref "CS Mux") (pin "7") (pinfunction "S4_7") (pintype "passive+no_connect"))
    )
    (net (code "78") (name "unconnected-(DigiPot 1-B-Pad5)") (class "Default")
      (node (ref "DigiPot 1") (pin "5") (pinfunction "B_5") (pintype "passive+no_connect"))
    )
    (net (code "79") (name "unconnected-(DigiPot 1-DIN-Pad10)") (class "Default")
      (node (ref "DigiPot 1") (pin "10") (pinfunction "DIN_10") (pintype "passive+no_connect"))
    )
    (net (code "80") (name "unconnected-(DigiPot 1-RDY-Pad14)") (class "Default")
      (node (ref "DigiPot 1") (pin "14") (pinfunction "RDY_14") (pintype "passive+no_connect"))
    )
    (net (code "81") (name "unconnected-(DigiPot 2-B-Pad5)") (class "Default")
      (node (ref "DigiPot 2") (pin "5") (pinfunction "B_5") (pintype "passive+no_connect"))
    )
    (net (code "82") (name "unconnected-(DigiPot 2-DIN-Pad10)") (class "Default")
      (node (ref "DigiPot 2") (pin "10") (pinfunction "DIN_10") (pintype "passive+no_connect"))
    )
    (net (code "83") (name "unconnected-(DigiPot 2-RDY-Pad14)") (class "Default")
      (node (ref "DigiPot 2") (pin "14") (pinfunction "RDY_14") (pintype "passive+no_connect"))
    )
    (net (code "84") (name "unconnected-(DigiPot 3-B-Pad5)") (class "Default")
      (node (ref "DigiPot 3") (pin "5") (pinfunction "B_5") (pintype "passive+no_connect"))
    )
    (net (code "85") (name "unconnected-(DigiPot 3-DIN-Pad10)") (class "Default")
      (node (ref "DigiPot 3") (pin "10") (pinfunction "DIN_10") (pintype "passive+no_connect"))
    )
    (net (code "86") (name "unconnected-(DigiPot 3-RDY-Pad14)") (class "Default")
      (node (ref "DigiPot 3") (pin "14") (pinfunction "RDY_14") (pintype "passive+no_connect"))
    )
    (net (code "87") (name "unconnected-(HS Mux-S4-Pad7)") (class "Default")
      (node (ref "HS Mux") (pin "7") (pinfunction "S4_7") (pintype "passive+no_connect"))
    )
    (net (code "88") (name "unconnected-(Motor1-Pad3)") (class "Default")
      (node (ref "Motor1") (pin "3") (pinfunction "3_3") (pintype "passive+no_connect"))
    )
    (net (code "89") (name "unconnected-(Motor2-Pad3)") (class "Default")
      (node (ref "Motor2") (pin "3") (pinfunction "3_3") (pintype "passive+no_connect"))
    )
    (net (code "90") (name "unconnected-(Motor3-Pad3)") (class "Default")
      (node (ref "Motor3") (pin "3") (pinfunction "3_3") (pintype "passive+no_connect"))
    )
    (net (code "91") (name "unconnected-(Sun Conn-Pad17)") (class "Default")
      (node (ref "Sun Conn") (pin "17") (pinfunction "17_17") (pintype "passive+no_connect"))
    )
    (net (code "92") (name "unconnected-(Sun Conn-Pad18)") (class "Default")
      (node (ref "Sun Conn") (pin "18") (pinfunction "18_18") (pintype "passive+no_connect"))
    )
    (net (code "93") (name "unconnected-(Teensy 3.2 Headers-3.3V-Pad16)") (class "Default")
      (node (ref "Teensy 3.2 Headers") (pin "16") (pinfunction "3.3V_16") (pintype "power_in+no_connect"))
    )
    (net (code "94") (name "unconnected-(Teensy 3.2 Headers-A14{slash}DAC-Pad19)") (class "Default")
      (node (ref "Teensy 3.2 Headers") (pin "19") (pinfunction "A14/DAC_19") (pintype "bidirectional+no_connect"))
    )
    (net (code "95") (name "unconnected-(Teensy 3.2 Headers-GND-Pad17)") (class "Default")
      (node (ref "Teensy 3.2 Headers") (pin "17") (pinfunction "GND_17") (pintype "power_in+no_connect"))
    )
    (net (code "96") (name "unconnected-(Teensy 3.2 Headers-Program-Pad18)") (class "Default")
      (node (ref "Teensy 3.2 Headers") (pin "18") (pinfunction "Program_18") (pintype "passive+no_connect"))
    )
    (net (code "97") (name "unconnected-(Teensy 3.2 Headers-VBAT-Pad15)") (class "Default")
      (node (ref "Teensy 3.2 Headers") (pin "15") (pinfunction "VBAT_15") (pintype "passive+no_connect"))
    )
  )
)
